# power.net
KiCad netlist of a schematic drawn in Altium Designer
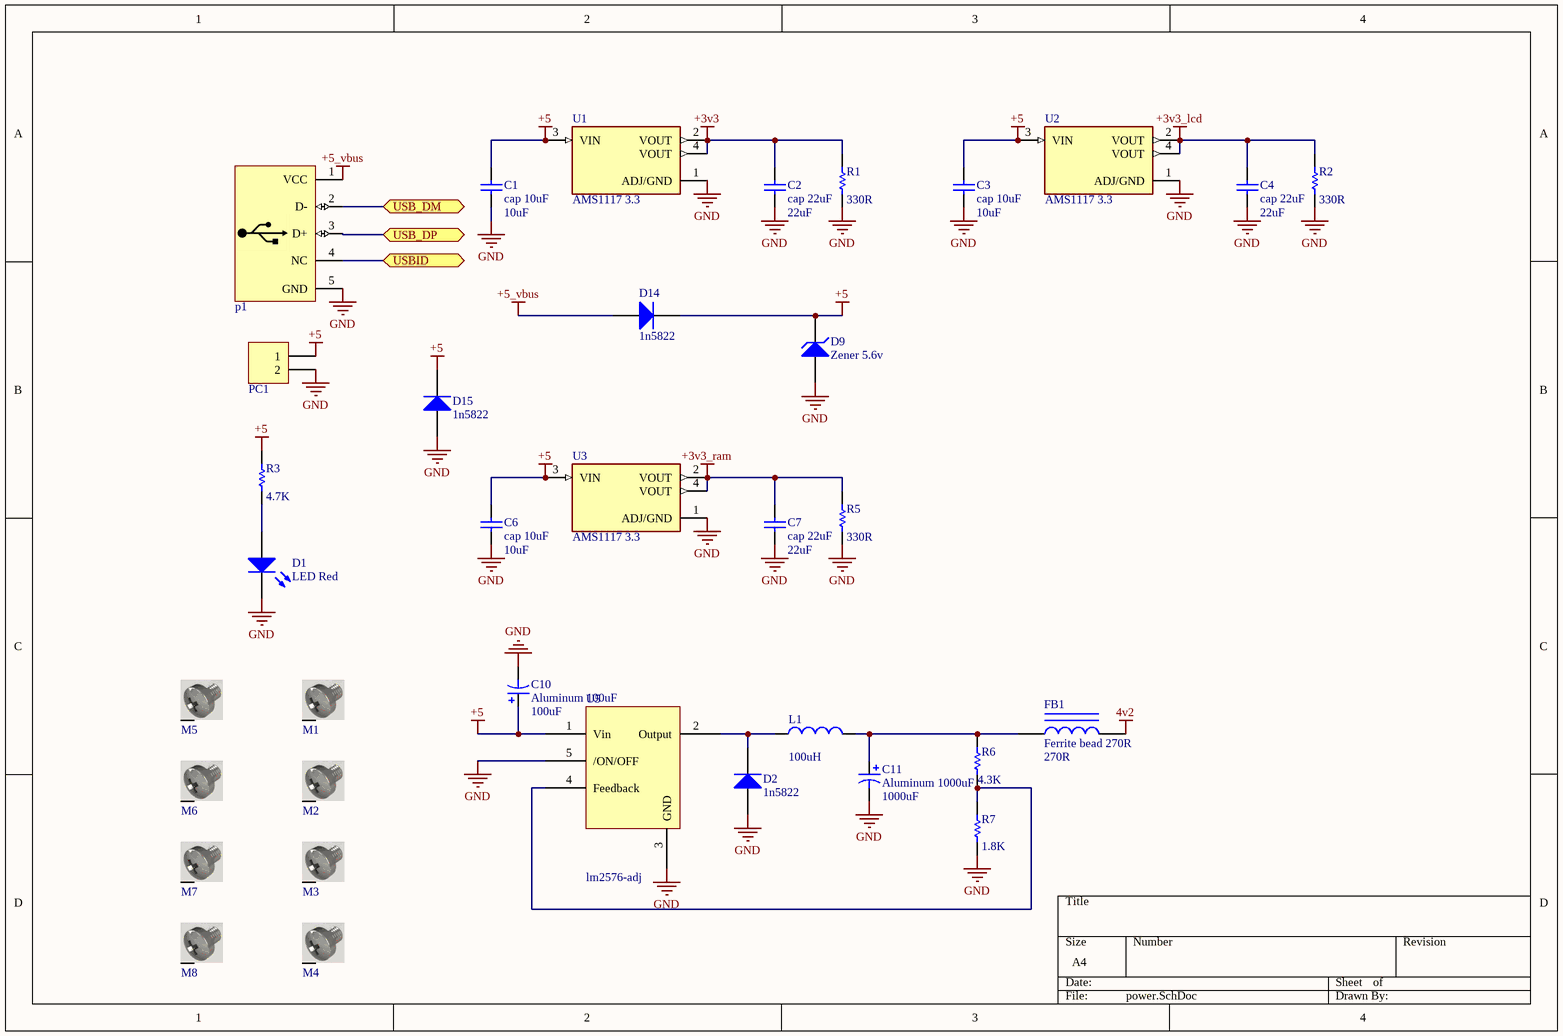
[diagram p0: power.SchDoc]

(export (version "E")
  (design (tool "Eeschema 10.0.6"))
  (components
    (comp (ref "C1")
      (value "cap 10uF")
      (footprint "Cap 805")
      (description "Capacitor")
      (fields (field (name "ALTIUM_VALUE") "10uF") (field (name "PUBLISHER") "Altium Limited"))
      (libsource (lib "Miscellaneous Devices") (part "Cap"))
    )
    (comp (ref "C2")
      (value "cap 22uF")
      (footprint "Cap 805")
      (description "Capacitor")
      (fields (field (name "ALTIUM_VALUE") "22uF") (field (name "PUBLISHER") "Altium Limited"))
      (libsource (lib "Miscellaneous Devices") (part "Cap"))
    )
    (comp (ref "C3")
      (value "cap 10uF")
      (footprint "Cap 805")
      (description "Capacitor")
      (fields (field (name "ALTIUM_VALUE") "10uF") (field (name "PUBLISHER") "Altium Limited"))
      (libsource (lib "Miscellaneous Devices") (part "Cap"))
    )
    (comp (ref "C4")
      (value "cap 22uF")
      (footprint "Cap 805")
      (description "Capacitor")
      (fields (field (name "ALTIUM_VALUE") "22uF") (field (name "PUBLISHER") "Altium Limited"))
      (libsource (lib "Miscellaneous Devices") (part "Cap"))
    )
    (comp (ref "C6")
      (value "cap 10uF")
      (footprint "Cap 805")
      (description "Capacitor")
      (fields (field (name "ALTIUM_VALUE") "10uF") (field (name "PUBLISHER") "Altium Limited"))
      (libsource (lib "Miscellaneous Devices") (part "Cap"))
    )
    (comp (ref "C7")
      (value "cap 22uF")
      (footprint "Cap 805")
      (description "Capacitor")
      (fields (field (name "ALTIUM_VALUE") "22uF") (field (name "PUBLISHER") "Altium Limited"))
      (libsource (lib "Miscellaneous Devices") (part "Cap"))
    )
    (comp (ref "C10")
      (value "Aluminum 100uF")
      (footprint "Cap SMD 100UF 35~50v")
      (description "Polarized Capacitor Aluminum")
      (fields (field (name "ALTIUM_VALUE") "100uF") (field (name "PUBLISHER") "Altium Limited"))
      (libsource (lib "Miscellaneous Devices") (part "Cap Pol1"))
    )
    (comp (ref "C11")
      (value "Aluminum 1000uF")
      (footprint "CAP SMD 1000UF 16V")
      (description "Polarized Capacitor Aluminum")
      (fields (field (name "ALTIUM_VALUE") "1000uF") (field (name "PUBLISHER") "Altium Limited"))
      (libsource (lib "Miscellaneous Devices") (part "Cap Pol1"))
    )
    (comp (ref "D1")
      (value "LED Red")
      (footprint "0805-LED")
      (description "LED SMD")
      (fields (field (name "PUBLISHER") "Altium Limited"))
      (libsource (lib "Miscellaneous Devices") (part "LED0"))
    )
    (comp (ref "D2")
      (value "1n5822")
      (footprint "SMA DIODE 2")
      (description "1 Amp schottky Diode")
      (fields (field (name "PUBLISHER") "Altium Limited"))
      (libsource (lib "Miscellaneous Devices") (part "Diode 1N4007"))
    )
    (comp (ref "D9")
      (value "Zener 5.6v")
      (footprint "Diode 1n4148 SMD")
      (description "Zener Diode")
      (fields (field (name "PUBLISHER") "Altium Limited"))
      (libsource (lib "Miscellaneous Devices") (part "D Zener"))
    )
    (comp (ref "D14")
      (value "1n5822")
      (footprint "SMA DIODE 2")
      (description "1 Amp schottky Diode")
      (fields (field (name "PUBLISHER") "Altium Limited"))
      (libsource (lib "Miscellaneous Devices") (part "Diode 1N4007"))
    )
    (comp (ref "D15")
      (value "1n5822")
      (footprint "SMA DIODE 2")
      (description "1 Amp schottky Diode")
      (fields (field (name "PUBLISHER") "Altium Limited"))
      (libsource (lib "Miscellaneous Devices") (part "Diode 1N4007"))
    )
    (comp (ref "FB1")
      (value "Ferrite bead 270R")
      (footprint "FB1206")
      (description "Ferrite bead smd 1206")
      (fields (field (name "ALTIUM_VALUE") "270R") (field (name "PUBLISHER") "Altium Limited"))
      (libsource (lib "Miscellaneous Devices") (part "Inductor Iron"))
    )
    (comp (ref "L1")
      (value "100uH")
      (footprint "inductor")
      (description "Inductor 12*12mm")
      (fields (field (name "Comment") "inductor 100uH") (field (name "PUBLISHER") "Altium Limited"))
      (libsource (lib "Miscellaneous Devices") (part "Inductor"))
    )
    (comp (ref "M1")
      (value "Spacer-ff 10mm")
      (footprint "Screw")
      (description "Board Screw With Spacer")
      (libsource (lib "My Library") (part "Board Screw"))
    )
    (comp (ref "M2")
      (value "Spacer-ff 10mm")
      (footprint "screw")
      (description "Board Screw With Spacer")
      (libsource (lib "My Library") (part "Board Screw"))
    )
    (comp (ref "M3")
      (value "Spacer-ff 10mm")
      (footprint "screw")
      (description "Board Screw With Spacer")
      (libsource (lib "My Library") (part "Board Screw"))
    )
    (comp (ref "M4")
      (value "Spacer-ff 10mm")
      (footprint "screw")
      (description "Board Screw With Spacer")
      (libsource (lib "My Library") (part "Board Screw"))
    )
    (comp (ref "M5")
      (value "Spacer-ff 10mm")
      (footprint "Screw")
      (description "Board Screw With Spacer")
      (libsource (lib "My Library") (part "Board Screw"))
    )
    (comp (ref "M6")
      (value "Spacer-ff 10mm")
      (footprint "screw")
      (description "Board Screw With Spacer")
      (libsource (lib "My Library") (part "Board Screw"))
    )
    (comp (ref "M7")
      (value "Spacer-ff 10mm")
      (footprint "screw")
      (description "Board Screw With Spacer")
      (libsource (lib "My Library") (part "Board Screw"))
    )
    (comp (ref "M8")
      (value "Spacer-ff 10mm")
      (footprint "screw")
      (description "Board Screw With Spacer")
      (libsource (lib "My Library") (part "Board Screw"))
    )
    (comp (ref "p1")
      (value "USB Connector")
      (footprint "USB_AB_BM_SHS")
      (description "USB Connector MICRO-B Type")
      (fields (field (name "DESIGNER") "ABBAS BASEREH") (field (name "PUBLISHER") "ABBAS BASEREH"))
      (libsource (lib "Altium (2)") (part "USB MICRO"))
    )
    (comp (ref "PC1")
      (value "Power Connector")
      (footprint "My_ Power_Connector")
      (description "white Power Connector")
      (libsource (lib "Altium library (www.AVRelec.com)") (part "Power Connector"))
    )
    (comp (ref "R1")
      (value "330R")
      (footprint "RES 0805 (2012X06L)")
      (description "Resistor")
      (fields (field (name "Comment") "Res 330R") (field (name "PUBLISHER") "Altium Limited"))
      (libsource (lib "Miscellaneous Devices") (part "Res1"))
    )
    (comp (ref "R2")
      (value "330R")
      (footprint "RES 0805 (2012X06L)")
      (description "Resistor")
      (fields (field (name "Comment") "Res 330R") (field (name "PUBLISHER") "Altium Limited"))
      (libsource (lib "Miscellaneous Devices") (part "Res1"))
    )
    (comp (ref "R3")
      (value "4.7K")
      (footprint "RES 0805 (2012X06L)")
      (description "Resistor")
      (fields (field (name "Comment") "Res 4.7K") (field (name "PUBLISHER") "Altium Limited"))
      (libsource (lib "Miscellaneous Devices") (part "Res1"))
    )
    (comp (ref "R5")
      (value "330R")
      (footprint "RES 0805 (2012X06L)")
      (description "Resistor")
      (fields (field (name "Comment") "Res 330R") (field (name "PUBLISHER") "Altium Limited"))
      (libsource (lib "Miscellaneous Devices") (part "Res1"))
    )
    (comp (ref "R6")
      (value "4.3K")
      (footprint "RES 0805 (2012X06L)")
      (description "Resistor")
      (fields (field (name "Comment") "Res 4.3K") (field (name "PUBLISHER") "Altium Limited"))
      (libsource (lib "Miscellaneous Devices") (part "Res1"))
    )
    (comp (ref "R7")
      (value "1.8K")
      (footprint "RES 0805 (2012X06L)")
      (description "Resistor")
      (fields (field (name "Comment") "Res 1.8K") (field (name "PUBLISHER") "Altium Limited"))
      (libsource (lib "Miscellaneous Devices") (part "Res1"))
    )
    (comp (ref "U1")
      (value "AMS1117 3.3")
      (footprint "SOT229P700X180-4N")
      (fields (field (name "MP") "AMS1117") (field (name "MF") "Seeed Technology"))
      (libsource (lib "AMS1117") (part "AMS1117"))
    )
    (comp (ref "U2")
      (value "AMS1117 3.3")
      (footprint "SOT229P700X180-4N")
      (fields (field (name "MP") "AMS1117") (field (name "MF") "Seeed Technology"))
      (libsource (lib "AMS1117") (part "AMS1117"))
    )
    (comp (ref "U3")
      (value "AMS1117 3.3")
      (footprint "SOT229P700X180-4N")
      (fields (field (name "MP") "AMS1117") (field (name "MF") "Seeed Technology"))
      (libsource (lib "AMS1117") (part "AMS1117"))
    )
    (comp (ref "U5") (value "lm2576-adj") (footprint "2596") (libsource (lib "No.2") (part "lm2596")))
  )
  (nets
    (net (code "1") (name "+3v3") (class "Default")
      (node (ref "C2") (pin "2") (pinfunction "2_2") (pintype "passive"))
      (node (ref "R1") (pin "2") (pinfunction "2_2") (pintype "passive"))
      (node (ref "U1") (pin "2") (pinfunction "VOUT_2") (pintype "output"))
      (node (ref "U1") (pin "4") (pinfunction "VOUT_4") (pintype "output"))
    )
    (net (code "2") (name "+3v3_lcd") (class "Default")
      (node (ref "C4") (pin "2") (pinfunction "2_2") (pintype "passive"))
      (node (ref "R2") (pin "2") (pinfunction "2_2") (pintype "passive"))
      (node (ref "U2") (pin "2") (pinfunction "VOUT_2") (pintype "output"))
      (node (ref "U2") (pin "4") (pinfunction "VOUT_4") (pintype "output"))
    )
    (net (code "3") (name "+3v3_ram") (class "Default")
      (node (ref "C7") (pin "2") (pinfunction "2_2") (pintype "passive"))
      (node (ref "R5") (pin "2") (pinfunction "2_2") (pintype "passive"))
      (node (ref "U3") (pin "2") (pinfunction "VOUT_2") (pintype "output"))
      (node (ref "U3") (pin "4") (pinfunction "VOUT_4") (pintype "output"))
    )
    (net (code "4") (name "+5") (class "Default")
      (node (ref "C1") (pin "2") (pinfunction "2_2") (pintype "passive"))
      (node (ref "C10") (pin "1") (pinfunction "1_1") (pintype "passive"))
      (node (ref "C3") (pin "2") (pinfunction "2_2") (pintype "passive"))
      (node (ref "C6") (pin "2") (pinfunction "2_2") (pintype "passive"))
      (node (ref "D14") (pin "2") (pinfunction "K_2") (pintype "passive"))
      (node (ref "D15") (pin "2") (pinfunction "K_2") (pintype "passive"))
      (node (ref "D9") (pin "2") (pinfunction "K_2") (pintype "passive"))
      (node (ref "PC1") (pin "1") (pinfunction "1_1") (pintype "passive"))
      (node (ref "R3") (pin "2") (pinfunction "2_2") (pintype "passive"))
      (node (ref "U1") (pin "3") (pinfunction "VIN_3") (pintype "input"))
      (node (ref "U2") (pin "3") (pinfunction "VIN_3") (pintype "input"))
      (node (ref "U3") (pin "3") (pinfunction "VIN_3") (pintype "input"))
      (node (ref "U5") (pin "1") (pinfunction "Vin_1") (pintype "power_in"))
    )
    (net (code "5") (name "+5_vbus") (class "Default")
      (node (ref "D14") (pin "1") (pinfunction "A_1") (pintype "passive"))
      (node (ref "p1") (pin "1") (pinfunction "VCC_1") (pintype "power_in"))
    )
    (net (code "6") (name "/USBID") (class "Default")
      (node (ref "p1") (pin "4") (pinfunction "NC_4") (pintype "passive"))
    )
    (net (code "7") (name "/USB_DM") (class "Default")
      (node (ref "p1") (pin "2") (pinfunction "D-_2") (pintype "bidirectional"))
    )
    (net (code "8") (name "/USB_DP") (class "Default")
      (node (ref "p1") (pin "3") (pinfunction "D+_3") (pintype "bidirectional"))
    )
    (net (code "9") (name "4v2") (class "Default")
      (node (ref "FB1") (pin "2") (pinfunction "2_2") (pintype "passive"))
    )
    (net (code "10") (name "GND") (class "Default")
      (node (ref "C1") (pin "1") (pinfunction "1_1") (pintype "passive"))
      (node (ref "C10") (pin "2") (pinfunction "2_2") (pintype "passive"))
      (node (ref "C11") (pin "2") (pinfunction "2_2") (pintype "passive"))
      (node (ref "C2") (pin "1") (pinfunction "1_1") (pintype "passive"))
      (node (ref "C3") (pin "1") (pinfunction "1_1") (pintype "passive"))
      (node (ref "C4") (pin "1") (pinfunction "1_1") (pintype "passive"))
      (node (ref "C6") (pin "1") (pinfunction "1_1") (pintype "passive"))
      (node (ref "C7") (pin "1") (pinfunction "1_1") (pintype "passive"))
      (node (ref "D1") (pin "2") (pinfunction "K_2") (pintype "passive"))
      (node (ref "D15") (pin "1") (pinfunction "A_1") (pintype "passive"))
      (node (ref "D2") (pin "1") (pinfunction "A_1") (pintype "passive"))
      (node (ref "D9") (pin "1") (pinfunction "A_1") (pintype "passive"))
      (node (ref "PC1") (pin "2") (pinfunction "2_2") (pintype "passive"))
      (node (ref "R1") (pin "1") (pinfunction "1_1") (pintype "passive"))
      (node (ref "R2") (pin "1") (pinfunction "1_1") (pintype "passive"))
      (node (ref "R5") (pin "1") (pinfunction "1_1") (pintype "passive"))
      (node (ref "R7") (pin "1") (pinfunction "1_1") (pintype "passive"))
      (node (ref "U1") (pin "1") (pinfunction "ADJ/GND_1") (pintype "power_in"))
      (node (ref "U2") (pin "1") (pinfunction "ADJ/GND_1") (pintype "power_in"))
      (node (ref "U3") (pin "1") (pinfunction "ADJ/GND_1") (pintype "power_in"))
      (node (ref "U5") (pin "3") (pinfunction "GND_3") (pintype "power_in"))
      (node (ref "U5") (pin "5") (pinfunction "/ON/OFF_5") (pintype "power_in"))
      (node (ref "p1") (pin "5") (pinfunction "GND_5") (pintype "power_in"))
    )
    (net (code "11") (name "Net-(C11-Pad1)") (class "Default")
      (node (ref "C11") (pin "1") (pinfunction "1_1") (pintype "passive"))
      (node (ref "FB1") (pin "1") (pinfunction "1_1") (pintype "passive"))
      (node (ref "L1") (pin "2") (pinfunction "2_2") (pintype "passive"))
      (node (ref "R6") (pin "2") (pinfunction "2_2") (pintype "passive"))
    )
    (net (code "12") (name "Net-(D1-A)") (class "Default")
      (node (ref "D1") (pin "1") (pinfunction "A_1") (pintype "passive"))
      (node (ref "R3") (pin "1") (pinfunction "1_1") (pintype "passive"))
    )
    (net (code "13") (name "Net-(D2-K)") (class "Default")
      (node (ref "D2") (pin "2") (pinfunction "K_2") (pintype "passive"))
      (node (ref "L1") (pin "1") (pinfunction "1_1") (pintype "passive"))
      (node (ref "U5") (pin "2") (pinfunction "Output_2") (pintype "power_in"))
    )
    (net (code "14") (name "Net-(U5-Feedback)") (class "Default")
      (node (ref "R6") (pin "1") (pinfunction "1_1") (pintype "passive"))
      (node (ref "R7") (pin "2") (pinfunction "2_2") (pintype "passive"))
      (node (ref "U5") (pin "4") (pinfunction "Feedback_4") (pintype "power_in"))
    )
    (net (code "15") (name "unconnected-(M1-PadS)") (class "Default")
      (node (ref "M1") (pin "S") (pinfunction "S_S") (pintype "passive"))
    )
    (net (code "16") (name "unconnected-(M2-PadS)") (class "Default")
      (node (ref "M2") (pin "S") (pinfunction "S_S") (pintype "passive"))
    )
    (net (code "17") (name "unconnected-(M3-PadS)") (class "Default")
      (node (ref "M3") (pin "S") (pinfunction "S_S") (pintype "passive"))
    )
    (net (code "18") (name "unconnected-(M4-PadS)") (class "Default")
      (node (ref "M4") (pin "S") (pinfunction "S_S") (pintype "passive"))
    )
    (net (code "19") (name "unconnected-(M5-PadS)") (class "Default")
      (node (ref "M5") (pin "S") (pinfunction "S_S") (pintype "passive"))
    )
    (net (code "20") (name "unconnected-(M6-PadS)") (class "Default")
      (node (ref "M6") (pin "S") (pinfunction "S_S") (pintype "passive"))
    )
    (net (code "21") (name "unconnected-(M7-PadS)") (class "Default")
      (node (ref "M7") (pin "S") (pinfunction "S_S") (pintype "passive"))
    )
    (net (code "22") (name "unconnected-(M8-PadS)") (class "Default")
      (node (ref "M8") (pin "S") (pinfunction "S_S") (pintype "passive"))
    )
  )
)
